# cart.net
KiCad netlist of a schematic drawn in EAGLE
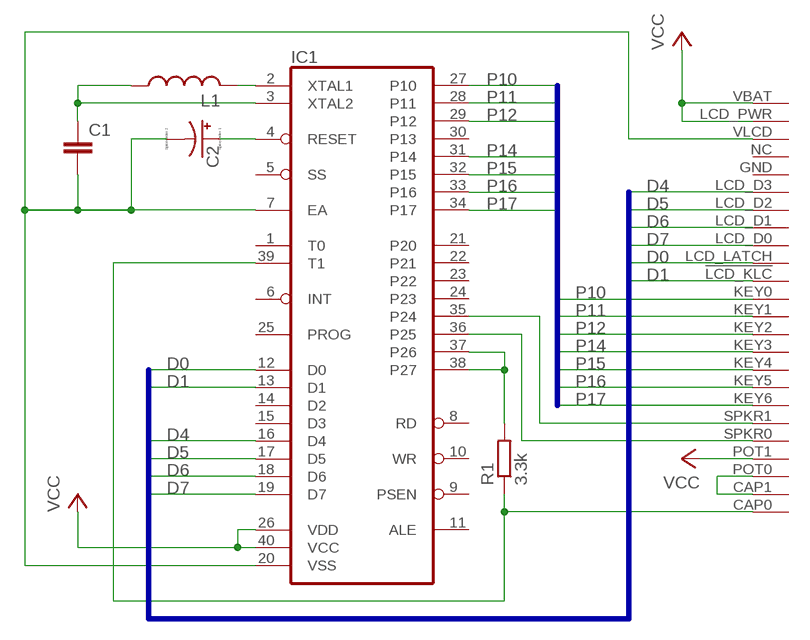
[diagram p0: schematic, sheet 1]

(export (version "E")
  (design (tool "Eeschema 10.0.6"))
  (components
    (comp (ref "C1")
      (value "C-EU050-024X044")
      (footprint "eagle-import:C050-024X044")
      (libsource (lib "eagle-import") (part "C-EU050-024X044"))
    )
    (comp (ref "C2")
      (value "CPOL-USE2.5-5")
      (footprint "eagle-import:E2,5-5")
      (libsource (lib "eagle-import") (part "CPOL-USE2.5-5"))
    )
    (comp (ref "IC1")
      (value "8748")
      (footprint "eagle-import:DIL40")
      (libsource (lib "eagle-import") (part "8748"))
    )
    (comp (ref "L1")
      (value "L-US0207/10")
      (footprint "eagle-import:0207_10")
      (libsource (lib "eagle-import") (part "L-US0207/10"))
    )
    (comp (ref "R1")
      (value "3.3k")
      (footprint "eagle-import:0204_7")
      (libsource (lib "eagle-import") (part "R-EU_0204/7"))
    )
    (comp (ref "U$1")
      (value "CONNECTOR")
      (footprint "eagle-import:CONNECTOR")
      (libsource (lib "eagle-import") (part "CONNECTOR"))
    )
  )
  (nets
    (net (code "1") (name "/D0") (class "Default")
      (node (ref "IC1") (pin "12") (pinfunction "D0_12") (pintype "bidirectional"))
      (node (ref "U$1") (pin "LCD_LATCH") (pinfunction "LCD_LATCH_LCD_LATCH") (pintype "output"))
    )
    (net (code "2") (name "/D1") (class "Default")
      (node (ref "IC1") (pin "13") (pinfunction "D1_13") (pintype "bidirectional"))
      (node (ref "U$1") (pin "!LCD_KLC") (pinfunction "LCD_CLK_!LCD_KLC") (pintype "output"))
    )
    (net (code "3") (name "/D4") (class "Default")
      (node (ref "IC1") (pin "16") (pinfunction "D4_16") (pintype "bidirectional"))
      (node (ref "U$1") (pin "LCD_D3") (pinfunction "LCD_D3_LCD_D3") (pintype "output"))
    )
    (net (code "4") (name "/D5") (class "Default")
      (node (ref "IC1") (pin "17") (pinfunction "D5_17") (pintype "bidirectional"))
      (node (ref "U$1") (pin "LCD_D2") (pinfunction "LCD_D2_LCD_D2") (pintype "output"))
    )
    (net (code "5") (name "/D6") (class "Default")
      (node (ref "IC1") (pin "18") (pinfunction "D6_18") (pintype "bidirectional"))
      (node (ref "U$1") (pin "LCD_D1") (pinfunction "LCD_D1_LCD_D1") (pintype "output"))
    )
    (net (code "6") (name "/D7") (class "Default")
      (node (ref "IC1") (pin "19") (pinfunction "D7_19") (pintype "bidirectional"))
      (node (ref "U$1") (pin "LCD_D0") (pinfunction "LCD_D0_LCD_D0") (pintype "output"))
    )
    (net (code "7") (name "/GND") (class "Default")
      (node (ref "U$1") (pin "GND") (pinfunction "GND_GND") (pintype "power_in"))
    )
    (net (code "8") (name "/P10") (class "Default")
      (node (ref "IC1") (pin "27") (pinfunction "P10_27") (pintype "bidirectional"))
      (node (ref "U$1") (pin "KEY0") (pinfunction "KEY0_KEY0") (pintype "input"))
    )
    (net (code "9") (name "/P11") (class "Default")
      (node (ref "IC1") (pin "28") (pinfunction "P11_28") (pintype "bidirectional"))
      (node (ref "U$1") (pin "KEY1") (pinfunction "KEY1_KEY1") (pintype "input"))
    )
    (net (code "10") (name "/P12") (class "Default")
      (node (ref "IC1") (pin "29") (pinfunction "P12_29") (pintype "bidirectional"))
      (node (ref "U$1") (pin "KEY2") (pinfunction "KEY2_KEY2") (pintype "input"))
    )
    (net (code "11") (name "/P14") (class "Default")
      (node (ref "IC1") (pin "31") (pinfunction "P14_31") (pintype "bidirectional"))
      (node (ref "U$1") (pin "KEY3") (pinfunction "KEY3_KEY3") (pintype "output"))
    )
    (net (code "12") (name "/P15") (class "Default")
      (node (ref "IC1") (pin "32") (pinfunction "P15_32") (pintype "bidirectional"))
      (node (ref "U$1") (pin "KEY4") (pinfunction "KEY4_KEY4") (pintype "output"))
    )
    (net (code "13") (name "/P16") (class "Default")
      (node (ref "IC1") (pin "33") (pinfunction "P16_33") (pintype "bidirectional"))
      (node (ref "U$1") (pin "KEY5") (pinfunction "KEY5_KEY5") (pintype "output"))
    )
    (net (code "14") (name "/P17") (class "Default")
      (node (ref "IC1") (pin "34") (pinfunction "P17_34") (pintype "bidirectional"))
      (node (ref "U$1") (pin "KEY6") (pinfunction "KEY6_KEY6") (pintype "output"))
    )
    (net (code "15") (name "Net-(IC1-EA)") (class "Default")
      (node (ref "C1") (pin "2") (pinfunction "2_2") (pintype "passive"))
      (node (ref "C2") (pin "-") (pinfunction "-_-") (pintype "passive"))
      (node (ref "IC1") (pin "20") (pinfunction "VSS_20") (pintype "power_in"))
      (node (ref "IC1") (pin "7") (pinfunction "EA_7") (pintype "input"))
      (node (ref "U$1") (pin "VLCD") (pinfunction "VLCD_VLCD") (pintype "power_in"))
    )
    (net (code "16") (name "Net-(IC1-P24)") (class "Default")
      (node (ref "IC1") (pin "35") (pinfunction "P24_35") (pintype "bidirectional"))
      (node (ref "U$1") (pin "SPKR1") (pinfunction "SPKR1_SPKR1") (pintype "output"))
    )
    (net (code "17") (name "Net-(IC1-P25)") (class "Default")
      (node (ref "IC1") (pin "36") (pinfunction "P25_36") (pintype "bidirectional"))
      (node (ref "U$1") (pin "SPKR0") (pinfunction "SPKR0_SPKR0") (pintype "output"))
    )
    (net (code "18") (name "Net-(IC1-P26)") (class "Default")
      (node (ref "IC1") (pin "37") (pinfunction "P26_37") (pintype "bidirectional"))
      (node (ref "IC1") (pin "38") (pinfunction "P27_38") (pintype "bidirectional"))
      (node (ref "R1") (pin "2") (pinfunction "2_2") (pintype "passive"))
    )
    (net (code "19") (name "Net-(IC1-RESET)") (class "Default")
      (node (ref "C2") (pin "+") (pinfunction "+_+") (pintype "passive"))
      (node (ref "IC1") (pin "4") (pinfunction "RESET_4") (pintype "input"))
    )
    (net (code "20") (name "Net-(IC1-T1)") (class "Default")
      (node (ref "IC1") (pin "39") (pinfunction "T1_39") (pintype "input"))
      (node (ref "R1") (pin "1") (pinfunction "1_1") (pintype "passive"))
      (node (ref "U$1") (pin "CAP0") (pinfunction "CAP0_CAP0") (pintype "input"))
    )
    (net (code "21") (name "Net-(IC1-XTAL1)") (class "Default")
      (node (ref "IC1") (pin "2") (pinfunction "XTAL1_2") (pintype "input"))
      (node (ref "L1") (pin "2") (pinfunction "2_2") (pintype "passive"))
    )
    (net (code "22") (name "Net-(IC1-XTAL2)") (class "Default")
      (node (ref "C1") (pin "1") (pinfunction "1_1") (pintype "passive"))
      (node (ref "IC1") (pin "3") (pinfunction "XTAL2_3") (pintype "output"))
      (node (ref "L1") (pin "1") (pinfunction "1_1") (pintype "passive"))
    )
    (net (code "23") (name "Net-(U$1-PadCAP1)") (class "Default")
      (node (ref "U$1") (pin "CAP1") (pinfunction "CAP1_CAP1") (pintype "input"))
      (node (ref "U$1") (pin "POT0") (pinfunction "POT0_POT0") (pintype "bidirectional"))
    )
    (net (code "24") (name "VCC") (class "Default")
      (node (ref "IC1") (pin "26") (pinfunction "VDD_26") (pintype "power_in"))
      (node (ref "IC1") (pin "40") (pinfunction "VCC_40") (pintype "power_in"))
      (node (ref "U$1") (pin "LCD_PWR") (pinfunction "LCD_PWR_LCD_PWR") (pintype "output"))
      (node (ref "U$1") (pin "POT1") (pinfunction "POT1_POT1") (pintype "input"))
      (node (ref "U$1") (pin "VBAT") (pinfunction "VBAT_VBAT") (pintype "power_in"))
    )
    (net (code "25") (name "unconnected-(IC1-ALE-Pad11)") (class "Default")
      (node (ref "IC1") (pin "11") (pinfunction "ALE_11") (pintype "output"))
    )
    (net (code "26") (name "unconnected-(IC1-D2-Pad14)") (class "Default")
      (node (ref "IC1") (pin "14") (pinfunction "D2_14") (pintype "bidirectional"))
    )
    (net (code "27") (name "unconnected-(IC1-D3-Pad15)") (class "Default")
      (node (ref "IC1") (pin "15") (pinfunction "D3_15") (pintype "bidirectional"))
    )
    (net (code "28") (name "unconnected-(IC1-INT-Pad6)") (class "Default")
      (node (ref "IC1") (pin "6") (pinfunction "INT_6") (pintype "input"))
    )
    (net (code "29") (name "unconnected-(IC1-P13-Pad30)") (class "Default")
      (node (ref "IC1") (pin "30") (pinfunction "P13_30") (pintype "bidirectional"))
    )
    (net (code "30") (name "unconnected-(IC1-P20-Pad21)") (class "Default")
      (node (ref "IC1") (pin "21") (pinfunction "P20_21") (pintype "bidirectional"))
    )
    (net (code "31") (name "unconnected-(IC1-P21-Pad22)") (class "Default")
      (node (ref "IC1") (pin "22") (pinfunction "P21_22") (pintype "bidirectional"))
    )
    (net (code "32") (name "unconnected-(IC1-P22-Pad23)") (class "Default")
      (node (ref "IC1") (pin "23") (pinfunction "P22_23") (pintype "bidirectional"))
    )
    (net (code "33") (name "unconnected-(IC1-P23-Pad24)") (class "Default")
      (node (ref "IC1") (pin "24") (pinfunction "P23_24") (pintype "bidirectional"))
    )
    (net (code "34") (name "unconnected-(IC1-PROG-Pad25)") (class "Default")
      (node (ref "IC1") (pin "25") (pinfunction "PROG_25") (pintype "input"))
    )
    (net (code "35") (name "unconnected-(IC1-PSEN-Pad9)") (class "Default")
      (node (ref "IC1") (pin "9") (pinfunction "PSEN_9") (pintype "output"))
    )
    (net (code "36") (name "unconnected-(IC1-RD-Pad8)") (class "Default")
      (node (ref "IC1") (pin "8") (pinfunction "RD_8") (pintype "output"))
    )
    (net (code "37") (name "unconnected-(IC1-SS-Pad5)") (class "Default")
      (node (ref "IC1") (pin "5") (pinfunction "SS_5") (pintype "input"))
    )
    (net (code "38") (name "unconnected-(IC1-T0-Pad1)") (class "Default")
      (node (ref "IC1") (pin "1") (pinfunction "T0_1") (pintype "input"))
    )
    (net (code "39") (name "unconnected-(IC1-WR-Pad10)") (class "Default")
      (node (ref "IC1") (pin "10") (pinfunction "WR_10") (pintype "output"))
    )
    (net (code "40") (name "unconnected-(U$1-PadNC)") (class "Default")
      (node (ref "U$1") (pin "NC") (pinfunction "NC_NC") (pintype "no_connect"))
    )
  )
)
